# design.net
KiCad netlist of a schematic drawn in EasyEDA Pro
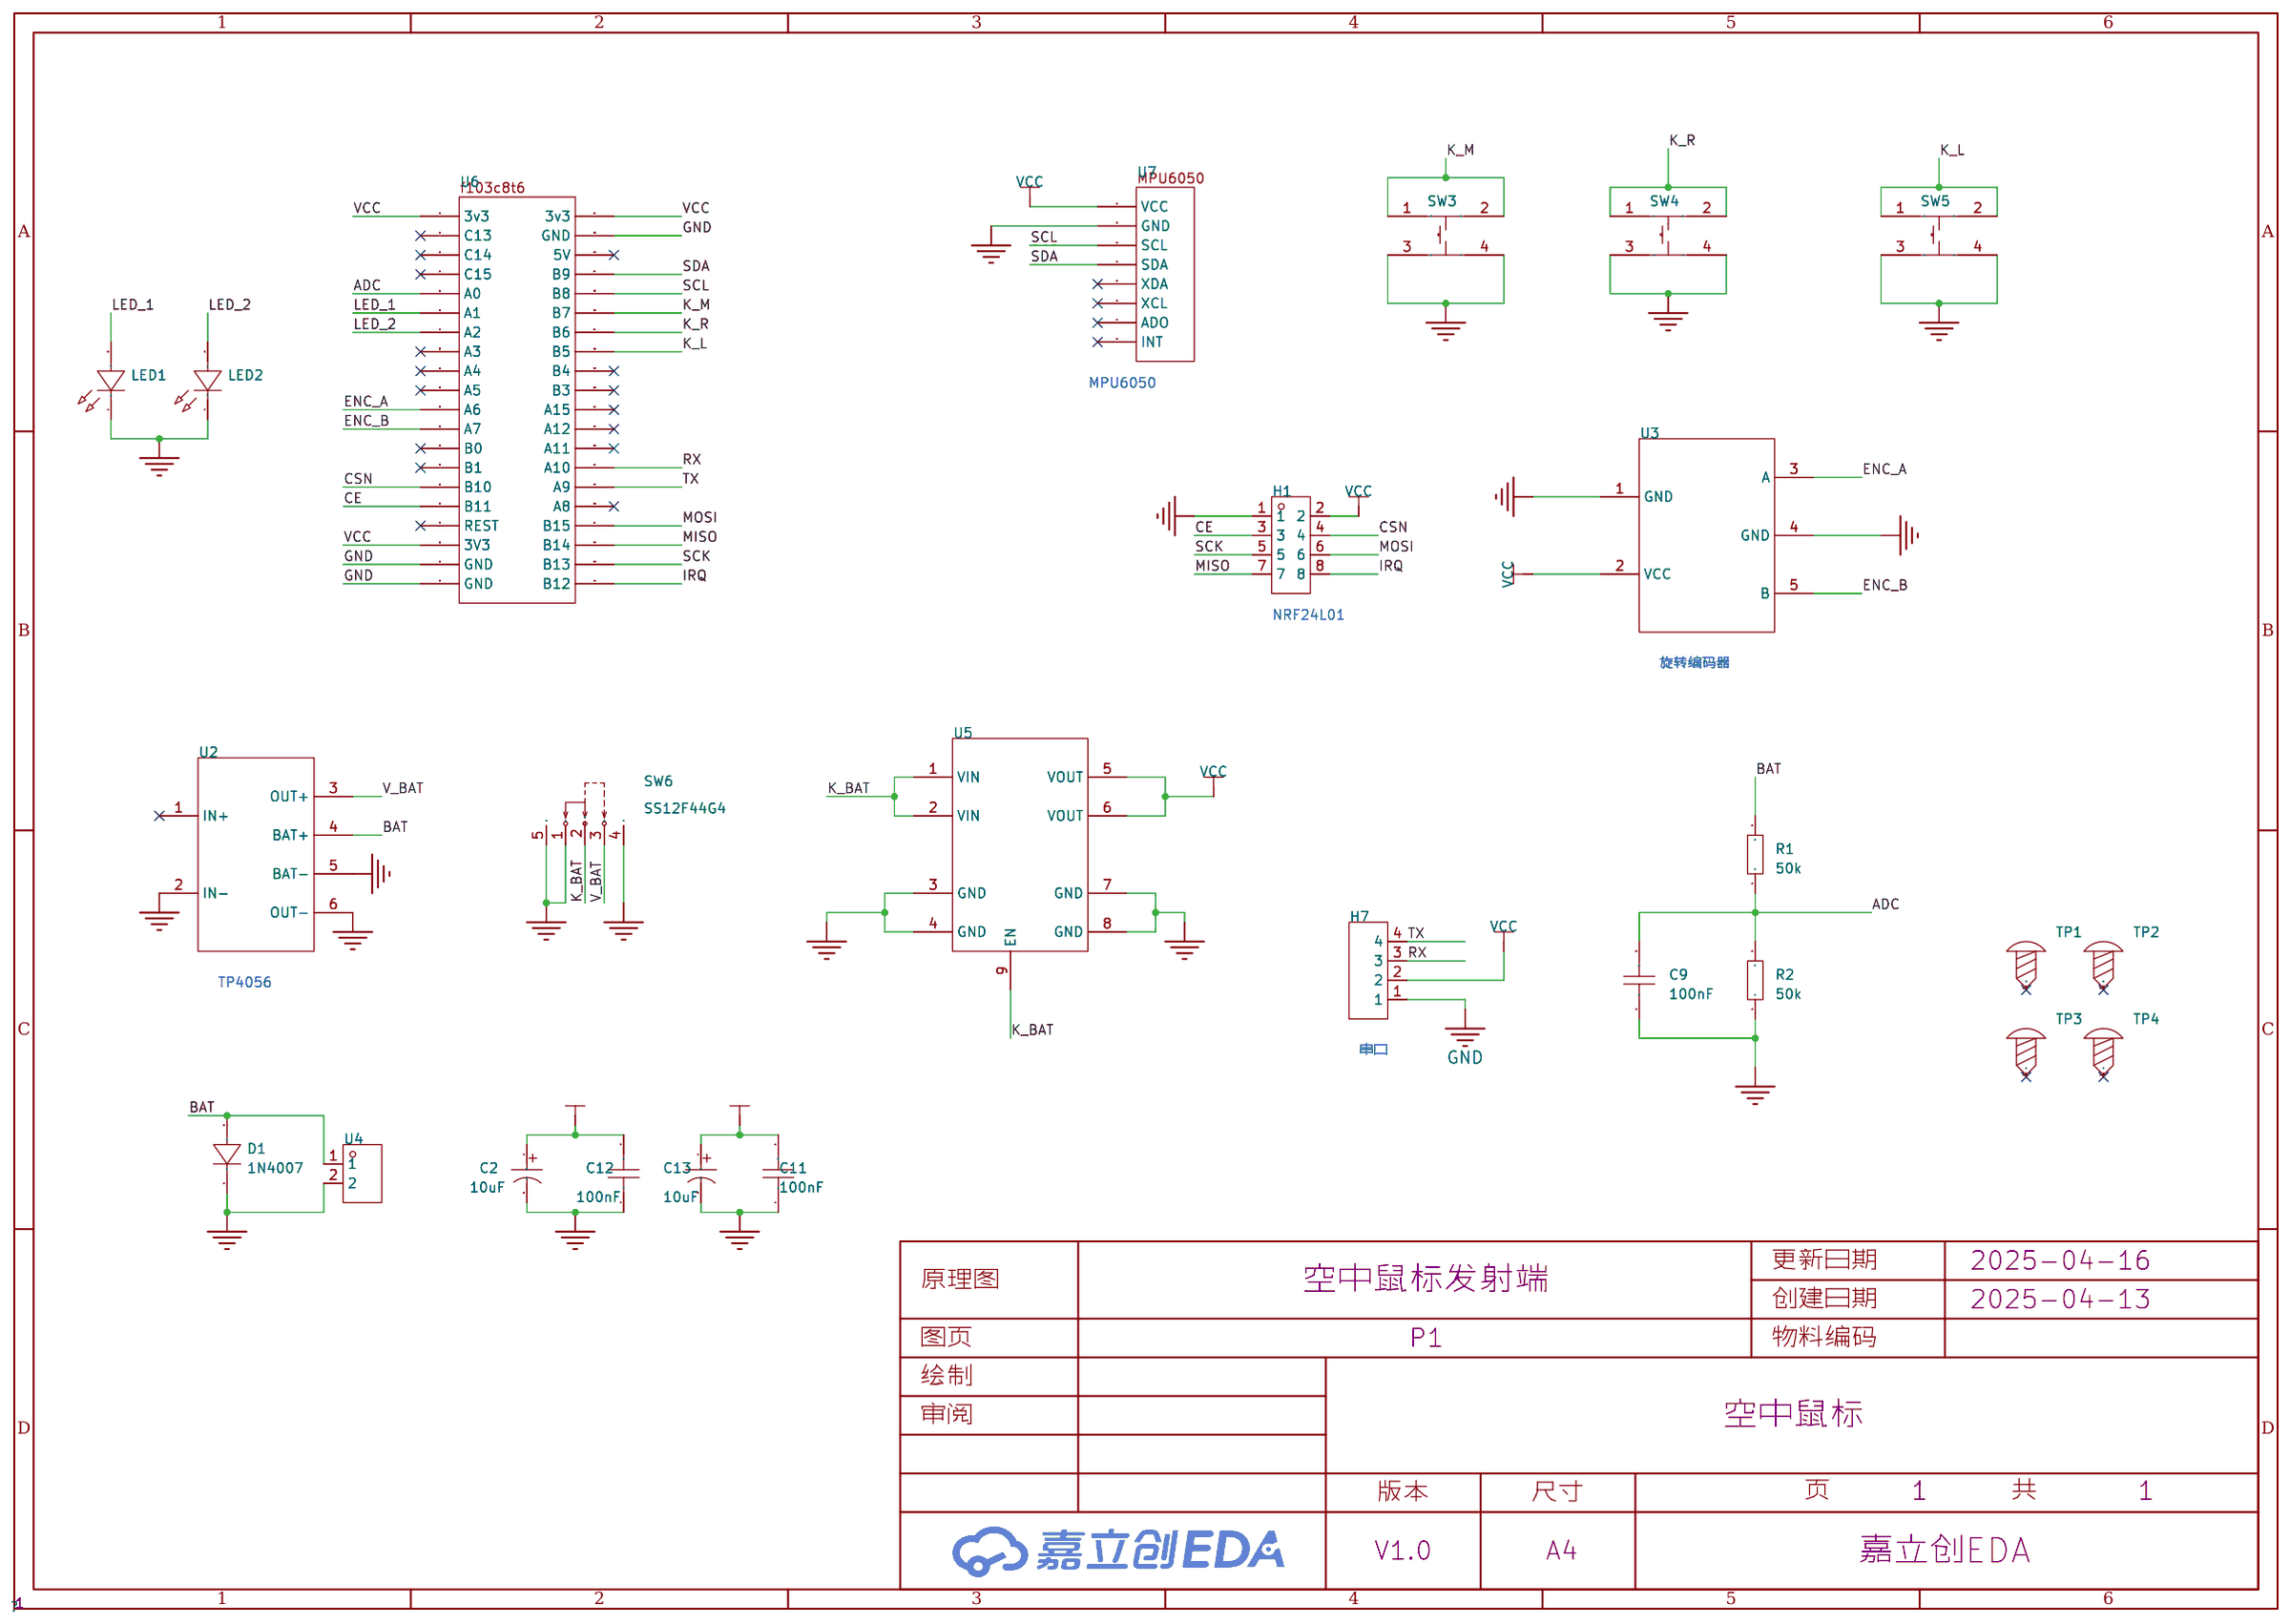
[diagram p0: schematic sheet]

(export (version "E")
  (design (tool "Eeschema 10.0.6"))
  (components
    (comp (ref "C2")
      (value "10uF")
      (footprint "easyedapro:CAP-SMD_BD4.0-L4.3-W4.3-FD")
      (description "容值:10uF;精度:±20%;额定电压:35V;纹波电流:15mA@120Hz;等效串联电阻(ESR):-;")
      (fields (field (name "Manufacturer Part") "RVT1V100M0405") (field (name "Manufacturer") "ROQANG(容强)"))
      (libsource (lib "easyedapro") (part "RVT1V100M0405-C72485"))
    )
    (comp (ref "C9")
      (value "100nF")
      (footprint "easyedapro:C0603")
      (libsource (lib "easyedapro") (part "CapAcitance"))
    )
    (comp (ref "C11")
      (value "100nF")
      (footprint "easyedapro:C0603")
      (description "容值:100nF;精度:±10%;额定电压:50V;材质(温度系数):X7R;")
      (fields
        (field (name "Manufacturer Part") "CC0603KRX7R9BB104")
        (field (name "Manufacturer") "YAGEO(国巨)")
      )
      (libsource (lib "easyedapro") (part "CC0603KRX7R9BB104"))
    )
    (comp (ref "C12")
      (value "100nF")
      (footprint "easyedapro:C0603")
      (description "容值:100nF;精度:±10%;额定电压:50V;材质(温度系数):X7R;")
      (fields
        (field (name "Manufacturer Part") "CC0603KRX7R9BB104")
        (field (name "Manufacturer") "YAGEO(国巨)")
      )
      (libsource (lib "easyedapro") (part "CC0603KRX7R9BB104"))
    )
    (comp (ref "C13")
      (value "10uF")
      (footprint "easyedapro:CAP-SMD_BD4.0-L4.3-W4.3-FD")
      (description "容值:10uF;精度:±20%;额定电压:35V;纹波电流:15mA@120Hz;等效串联电阻(ESR):-;")
      (fields (field (name "Manufacturer Part") "RVT1V100M0405") (field (name "Manufacturer") "ROQANG(容强)"))
      (libsource (lib "easyedapro") (part "RVT1V100M0405-C72485"))
    )
    (comp (ref "D1")
      (value "1N4007")
      (footprint "easyedapro:SMA_L4.3-W2.5-LS5.0-RD")
      (description "二极管配置:独立式;正向压降(Vf):1.1V@1A;直流反向耐压(Vr):1kV;整流电流:1A;")
      (fields (field (name "Manufacturer") "TWGMC(台湾迪嘉)"))
      (libsource (lib "easyedapro") (part "1N4007_C727081"))
    )
    (comp (ref "H1")
      (value "NRF24L01")
      (footprint "easyedapro:HDR-TH_8P-P2.54-V-F-R2-C4-S2.54")
      (fields (field (name "Manufacturer Part") "PM254V-12-08-H85") (field (name "Manufacturer") "XFCN(兴飞)"))
      (libsource (lib "easyedapro") (part "PM254V-12-08-H85_C2834799"))
    )
    (comp (ref "H7")
      (value "~")
      (footprint "easyedapro:HDR-TH_4P-P2.54-V-M")
      (libsource (lib "easyedapro") (part "PZ254V-11-04P"))
    )
    (comp (ref "LED1")
      (value "521-9210F")
      (footprint "easyedapro:LED-TH_BD3.0-P2.54-RD")
      (fields (field (name "Manufacturer") "Dialight"))
      (libsource (lib "easyedapro") (part "521-9210F"))
    )
    (comp (ref "LED2")
      (value "521-9210F")
      (footprint "easyedapro:LED-TH_BD3.0-P2.54-RD")
      (fields (field (name "Manufacturer") "Dialight"))
      (libsource (lib "easyedapro") (part "521-9210F"))
    )
    (comp (ref "R1") (value "50k") (footprint "easyedapro:R0603") (libsource (lib "easyedapro") (part "电阻")))
    (comp (ref "R2") (value "50k") (footprint "easyedapro:R0603") (libsource (lib "easyedapro") (part "电阻")))
    (comp (ref "SCREW1")
      (value "TP1")
      (footprint "easyedapro:M3螺丝")
      (libsource (lib "easyedapro") (part "螺丝孔"))
    )
    (comp (ref "SCREW2")
      (value "TP2")
      (footprint "easyedapro:M3螺丝")
      (libsource (lib "easyedapro") (part "螺丝孔"))
    )
    (comp (ref "SCREW3")
      (value "TP3")
      (footprint "easyedapro:M3螺丝")
      (libsource (lib "easyedapro") (part "螺丝孔"))
    )
    (comp (ref "SCREW4")
      (value "TP4")
      (footprint "easyedapro:M3螺丝")
      (libsource (lib "easyedapro") (part "螺丝孔"))
    )
    (comp (ref "SW3")
      (value "TS-1002-07026")
      (footprint "easyedapro:SW-TH_4P-L6.0-W6.0-P4.50-LS6.5")
      (description "电路结构:单刀单掷;按钮形状:圆形按钮;安装方式:直插;开关长度:6mm;开关宽度:6mm;开关高度:7mm;触点电流:50mA;额定电压(DC):12V;带灯:-;机械寿命:-;")
      (fields (field (name "Manufacturer") "XUNPU(讯普)"))
      (libsource (lib "easyedapro") (part "TS-1002-07026"))
    )
    (comp (ref "SW4")
      (value "TS-1002-07026")
      (footprint "easyedapro:SW-TH_4P-L6.0-W6.0-P4.50-LS6.5")
      (description "电路结构:单刀单掷;按钮形状:圆形按钮;安装方式:直插;开关长度:6mm;开关宽度:6mm;开关高度:7mm;触点电流:50mA;额定电压(DC):12V;带灯:-;机械寿命:-;")
      (fields (field (name "Manufacturer") "XUNPU(讯普)"))
      (libsource (lib "easyedapro") (part "TS-1002-07026"))
    )
    (comp (ref "SW5")
      (value "TS-1002-07026")
      (footprint "easyedapro:SW-TH_4P-L6.0-W6.0-P4.50-LS6.5")
      (description "电路结构:单刀单掷;按钮形状:圆形按钮;安装方式:直插;开关长度:6mm;开关宽度:6mm;开关高度:7mm;触点电流:50mA;额定电压(DC):12V;带灯:-;机械寿命:-;")
      (fields (field (name "Manufacturer") "XUNPU(讯普)"))
      (libsource (lib "easyedapro") (part "TS-1002-07026"))
    )
    (comp (ref "SW6")
      (value "SS12F44G4")
      (footprint "easyedapro:SW-TH_SHOU-HAN_SS12F44G4")
      (description "电路结构:单刀双掷;安装方式:直插;开关颜色:-;额定电流(DC):300mA;额定电压(DC):50V;额定电流(AC):-;额定电压(AC):-;机械寿命:5千次;")
      (fields (field (name "Manufacturer") "SHOU HAN(首韩)"))
      (libsource (lib "easyedapro") (part "SS12F44G4"))
    )
    (comp (ref "U2")
      (value "~")
      (footprint "easyedapro:TP4056")
      (libsource (lib "easyedapro") (part "TP4056模块"))
    )
    (comp (ref "U3") (value "~") (footprint "easyedapro:旋转编码器") (libsource (lib "easyedapro") (part "旋转编码器")))
    (comp (ref "U4")
      (value "XY-XHB2.54-2A21")
      (footprint "easyedapro:HDR-TH_2P-P2.50-H-F-W7.3-N")
      (description "插针结构:1x2P;间距:2.54mm;安装方式:弯插;总PIN数:2P;排数:1;每排PIN数:2;行距:2.54mm;额定电流:2A;工作温度范围:-25°C~+85°C;")
      (fields (field (name "Manufacturer") "XYECONN(辛译)"))
      (libsource (lib "easyedapro") (part "XY-XHB2.54-2A21"))
    )
    (comp (ref "U5")
      (value "~")
      (footprint "easyedapro:TPS63000")
      (libsource (lib "easyedapro") (part "TPS63000"))
    )
    (comp (ref "U6")
      (value "~")
      (footprint "easyedapro:stm32f103c8t6最小系统板")
      (libsource (lib "easyedapro") (part "stm32f103c8t6最小系统板"))
    )
    (comp (ref "U7")
      (value "~")
      (footprint "easyedapro:MPU6050")
      (libsource (lib "easyedapro") (part "MPU6050"))
    )
  )
  (nets
    (net (code "1") (name "/ADC") (class "Default")
      (node (ref "C9") (pin "2") (pinfunction "2_2") (pintype "input"))
      (node (ref "R1") (pin "1") (pinfunction "1_1") (pintype "input"))
      (node (ref "R2") (pin "2") (pinfunction "2_2") (pintype "input"))
      (node (ref "U6") (pin "5") (pinfunction "A0_5") (pintype "input"))
    )
    (net (code "2") (name "/BAT") (class "Default")
      (node (ref "D1") (pin "2") (pinfunction "A_2") (pintype "unspecified"))
      (node (ref "R1") (pin "2") (pinfunction "2_2") (pintype "input"))
      (node (ref "U2") (pin "4") (pinfunction "BAT+_4") (pintype "input"))
      (node (ref "U4") (pin "1") (pinfunction "1_1") (pintype "unspecified"))
    )
    (net (code "3") (name "/CE") (class "Default")
      (node (ref "H1") (pin "3") (pinfunction "3_3") (pintype "unspecified"))
      (node (ref "U6") (pin "16") (pinfunction "B11_16") (pintype "input"))
    )
    (net (code "4") (name "/CSN") (class "Default")
      (node (ref "H1") (pin "4") (pinfunction "4_4") (pintype "unspecified"))
      (node (ref "U6") (pin "15") (pinfunction "B10_15") (pintype "input"))
    )
    (net (code "5") (name "/ENC_A") (class "Default")
      (node (ref "U3") (pin "3") (pinfunction "A_3") (pintype "input"))
      (node (ref "U6") (pin "11") (pinfunction "A6_11") (pintype "input"))
    )
    (net (code "6") (name "/ENC_B") (class "Default")
      (node (ref "U3") (pin "5") (pinfunction "B_5") (pintype "input"))
      (node (ref "U6") (pin "12") (pinfunction "A7_12") (pintype "input"))
    )
    (net (code "7") (name "/IRQ") (class "Default")
      (node (ref "H1") (pin "8") (pinfunction "8_8") (pintype "unspecified"))
      (node (ref "U6") (pin "40") (pinfunction "B12_40") (pintype "input"))
    )
    (net (code "8") (name "/K_L") (class "Default")
      (node (ref "SW5") (pin "1") (pinfunction "1_1") (pintype "unspecified"))
      (node (ref "SW5") (pin "2") (pinfunction "2_2") (pintype "unspecified"))
      (node (ref "U6") (pin "28") (pinfunction "B5_28") (pintype "input"))
    )
    (net (code "9") (name "/K_M") (class "Default")
      (node (ref "SW3") (pin "1") (pinfunction "1_1") (pintype "unspecified"))
      (node (ref "SW3") (pin "2") (pinfunction "2_2") (pintype "unspecified"))
      (node (ref "U6") (pin "26") (pinfunction "B7_26") (pintype "input"))
    )
    (net (code "10") (name "/K_R") (class "Default")
      (node (ref "SW4") (pin "1") (pinfunction "1_1") (pintype "unspecified"))
      (node (ref "SW4") (pin "2") (pinfunction "2_2") (pintype "unspecified"))
      (node (ref "U6") (pin "27") (pinfunction "B6_27") (pintype "input"))
    )
    (net (code "11") (name "/LED_1") (class "Default")
      (node (ref "LED1") (pin "2") (pinfunction "A_2") (pintype "unspecified"))
      (node (ref "U6") (pin "6") (pinfunction "A1_6") (pintype "input"))
    )
    (net (code "12") (name "/LED_2") (class "Default")
      (node (ref "LED2") (pin "2") (pinfunction "A_2") (pintype "unspecified"))
      (node (ref "U6") (pin "7") (pinfunction "A2_7") (pintype "input"))
    )
    (net (code "13") (name "/MISO") (class "Default")
      (node (ref "H1") (pin "7") (pinfunction "7_7") (pintype "unspecified"))
      (node (ref "U6") (pin "38") (pinfunction "B14_38") (pintype "input"))
    )
    (net (code "14") (name "/MOSI") (class "Default")
      (node (ref "H1") (pin "6") (pinfunction "6_6") (pintype "unspecified"))
      (node (ref "U6") (pin "37") (pinfunction "B15_37") (pintype "input"))
    )
    (net (code "15") (name "/RX") (class "Default")
      (node (ref "H7") (pin "3") (pinfunction "3_3") (pintype "unspecified"))
      (node (ref "U6") (pin "34") (pinfunction "A10_34") (pintype "input"))
    )
    (net (code "16") (name "/SCK") (class "Default")
      (node (ref "H1") (pin "5") (pinfunction "5_5") (pintype "unspecified"))
      (node (ref "U6") (pin "39") (pinfunction "B13_39") (pintype "input"))
    )
    (net (code "17") (name "/SCL") (class "Default")
      (node (ref "U6") (pin "25") (pinfunction "B8_25") (pintype "input"))
      (node (ref "U7") (pin "3") (pinfunction "SCL_3") (pintype "input"))
    )
    (net (code "18") (name "/SDA") (class "Default")
      (node (ref "U6") (pin "24") (pinfunction "B9_24") (pintype "input"))
      (node (ref "U7") (pin "4") (pinfunction "SDA_4") (pintype "input"))
    )
    (net (code "19") (name "/TX") (class "Default")
      (node (ref "H7") (pin "4") (pinfunction "4_4") (pintype "unspecified"))
      (node (ref "U6") (pin "35") (pinfunction "A9_35") (pintype "input"))
    )
    (net (code "20") (name "/V_BAT") (class "Default")
      (node (ref "SW6") (pin "3") (pinfunction "3_3") (pintype "unspecified"))
      (node (ref "U2") (pin "3") (pinfunction "OUT+_3") (pintype "input"))
    )
    (net (code "21") (name "GND") (class "Default")
      (node (ref "C11") (pin "1") (pinfunction "1_1") (pintype "unspecified"))
      (node (ref "C12") (pin "1") (pinfunction "1_1") (pintype "unspecified"))
      (node (ref "C13") (pin "2") (pinfunction "2_2") (pintype "input"))
      (node (ref "C2") (pin "2") (pinfunction "2_2") (pintype "input"))
      (node (ref "C9") (pin "1") (pinfunction "1_1") (pintype "input"))
      (node (ref "D1") (pin "1") (pinfunction "K_1") (pintype "unspecified"))
      (node (ref "H1") (pin "1") (pinfunction "1_1") (pintype "unspecified"))
      (node (ref "H7") (pin "1") (pinfunction "1_1") (pintype "unspecified"))
      (node (ref "LED1") (pin "1") (pinfunction "K_1") (pintype "unspecified"))
      (node (ref "LED2") (pin "1") (pinfunction "K_1") (pintype "unspecified"))
      (node (ref "R2") (pin "1") (pinfunction "1_1") (pintype "input"))
      (node (ref "SW3") (pin "3") (pinfunction "3_3") (pintype "unspecified"))
      (node (ref "SW3") (pin "4") (pinfunction "4_4") (pintype "unspecified"))
      (node (ref "SW4") (pin "3") (pinfunction "3_3") (pintype "unspecified"))
      (node (ref "SW4") (pin "4") (pinfunction "4_4") (pintype "unspecified"))
      (node (ref "SW5") (pin "3") (pinfunction "3_3") (pintype "unspecified"))
      (node (ref "SW5") (pin "4") (pinfunction "4_4") (pintype "unspecified"))
      (node (ref "SW6") (pin "1") (pinfunction "1_1") (pintype "unspecified"))
      (node (ref "SW6") (pin "4") (pinfunction "4_4") (pintype "unspecified"))
      (node (ref "SW6") (pin "5") (pinfunction "5_5") (pintype "unspecified"))
      (node (ref "U2") (pin "2") (pinfunction "IN-_2") (pintype "input"))
      (node (ref "U2") (pin "5") (pinfunction "BAT-_5") (pintype "input"))
      (node (ref "U2") (pin "6") (pinfunction "OUT-_6") (pintype "input"))
      (node (ref "U3") (pin "1") (pinfunction "GND_1") (pintype "input"))
      (node (ref "U3") (pin "4") (pinfunction "GND_4") (pintype "input"))
      (node (ref "U4") (pin "2") (pinfunction "2_2") (pintype "unspecified"))
      (node (ref "U5") (pin "3") (pinfunction "GND_3") (pintype "input"))
      (node (ref "U5") (pin "4") (pinfunction "GND_4") (pintype "input"))
      (node (ref "U5") (pin "7") (pinfunction "GND_7") (pintype "input"))
      (node (ref "U5") (pin "8") (pinfunction "GND_8") (pintype "input"))
      (node (ref "U6") (pin "19") (pinfunction "GND_19") (pintype "input"))
      (node (ref "U6") (pin "20") (pinfunction "GND_20") (pintype "input"))
      (node (ref "U6") (pin "22") (pinfunction "GND_22") (pintype "input"))
      (node (ref "U7") (pin "2") (pinfunction "GND_2") (pintype "input"))
    )
    (net (code "22") (name "K_BAT") (class "Default")
      (node (ref "C12") (pin "2") (pinfunction "2_2") (pintype "unspecified"))
      (node (ref "C2") (pin "1") (pinfunction "1_1") (pintype "input"))
      (node (ref "SW6") (pin "2") (pinfunction "2_2") (pintype "unspecified"))
      (node (ref "U5") (pin "1") (pinfunction "VIN_1") (pintype "input"))
      (node (ref "U5") (pin "2") (pinfunction "VIN_2") (pintype "input"))
      (node (ref "U5") (pin "9") (pinfunction "EN_9") (pintype "input"))
    )
    (net (code "23") (name "VCC") (class "Default")
      (node (ref "C11") (pin "2") (pinfunction "2_2") (pintype "unspecified"))
      (node (ref "C13") (pin "1") (pinfunction "1_1") (pintype "input"))
      (node (ref "H1") (pin "2") (pinfunction "2_2") (pintype "unspecified"))
      (node (ref "H7") (pin "2") (pinfunction "2_2") (pintype "unspecified"))
      (node (ref "U3") (pin "2") (pinfunction "VCC_2") (pintype "input"))
      (node (ref "U5") (pin "5") (pinfunction "VOUT_5") (pintype "input"))
      (node (ref "U5") (pin "6") (pinfunction "VOUT_6") (pintype "input"))
      (node (ref "U6") (pin "1") (pinfunction "3v3_1") (pintype "input"))
      (node (ref "U6") (pin "18") (pinfunction "3V3_18") (pintype "input"))
      (node (ref "U6") (pin "21") (pinfunction "3v3_21") (pintype "input"))
      (node (ref "U7") (pin "1") (pinfunction "VCC_1") (pintype "input"))
    )
    (net (code "24") (name "unconnected-(SCREW1-Pad1)") (class "Default")
      (node (ref "SCREW1") (pin "1") (pinfunction "1_1") (pintype "input+no_connect"))
    )
    (net (code "25") (name "unconnected-(SCREW2-Pad1)") (class "Default")
      (node (ref "SCREW2") (pin "1") (pinfunction "1_1") (pintype "input+no_connect"))
    )
    (net (code "26") (name "unconnected-(SCREW3-Pad1)") (class "Default")
      (node (ref "SCREW3") (pin "1") (pinfunction "1_1") (pintype "input+no_connect"))
    )
    (net (code "27") (name "unconnected-(SCREW4-Pad1)") (class "Default")
      (node (ref "SCREW4") (pin "1") (pinfunction "1_1") (pintype "input+no_connect"))
    )
    (net (code "28") (name "unconnected-(U2-IN+-Pad1)") (class "Default")
      (node (ref "U2") (pin "1") (pinfunction "IN+_1") (pintype "input+no_connect"))
    )
    (net (code "29") (name "unconnected-(U6-5V-Pad23)") (class "Default")
      (node (ref "U6") (pin "23") (pinfunction "5V_23") (pintype "input+no_connect"))
    )
    (net (code "30") (name "unconnected-(U6-A3-Pad8)") (class "Default")
      (node (ref "U6") (pin "8") (pinfunction "A3_8") (pintype "input+no_connect"))
    )
    (net (code "31") (name "unconnected-(U6-A4-Pad9)") (class "Default")
      (node (ref "U6") (pin "9") (pinfunction "A4_9") (pintype "input+no_connect"))
    )
    (net (code "32") (name "unconnected-(U6-A5-Pad10)") (class "Default")
      (node (ref "U6") (pin "10") (pinfunction "A5_10") (pintype "input+no_connect"))
    )
    (net (code "33") (name "unconnected-(U6-A8-Pad36)") (class "Default")
      (node (ref "U6") (pin "36") (pinfunction "A8_36") (pintype "input+no_connect"))
    )
    (net (code "34") (name "unconnected-(U6-A11-Pad33)") (class "Default")
      (node (ref "U6") (pin "33") (pinfunction "A11_33") (pintype "input+no_connect"))
    )
    (net (code "35") (name "unconnected-(U6-A12-Pad32)") (class "Default")
      (node (ref "U6") (pin "32") (pinfunction "A12_32") (pintype "input+no_connect"))
    )
    (net (code "36") (name "unconnected-(U6-A15-Pad31)") (class "Default")
      (node (ref "U6") (pin "31") (pinfunction "A15_31") (pintype "input+no_connect"))
    )
    (net (code "37") (name "unconnected-(U6-B0-Pad13)") (class "Default")
      (node (ref "U6") (pin "13") (pinfunction "B0_13") (pintype "input+no_connect"))
    )
    (net (code "38") (name "unconnected-(U6-B1-Pad14)") (class "Default")
      (node (ref "U6") (pin "14") (pinfunction "B1_14") (pintype "input+no_connect"))
    )
    (net (code "39") (name "unconnected-(U6-B3-Pad30)") (class "Default")
      (node (ref "U6") (pin "30") (pinfunction "B3_30") (pintype "input+no_connect"))
    )
    (net (code "40") (name "unconnected-(U6-B4-Pad29)") (class "Default")
      (node (ref "U6") (pin "29") (pinfunction "B4_29") (pintype "input+no_connect"))
    )
    (net (code "41") (name "unconnected-(U6-C13-Pad2)") (class "Default")
      (node (ref "U6") (pin "2") (pinfunction "C13_2") (pintype "input+no_connect"))
    )
    (net (code "42") (name "unconnected-(U6-C14-Pad3)") (class "Default")
      (node (ref "U6") (pin "3") (pinfunction "C14_3") (pintype "input+no_connect"))
    )
    (net (code "43") (name "unconnected-(U6-C15-Pad4)") (class "Default")
      (node (ref "U6") (pin "4") (pinfunction "C15_4") (pintype "input+no_connect"))
    )
    (net (code "44") (name "unconnected-(U6-REST-Pad17)") (class "Default")
      (node (ref "U6") (pin "17") (pinfunction "REST_17") (pintype "input+no_connect"))
    )
    (net (code "45") (name "unconnected-(U7-ADO-Pad7)") (class "Default")
      (node (ref "U7") (pin "7") (pinfunction "ADO_7") (pintype "input+no_connect"))
    )
    (net (code "46") (name "unconnected-(U7-INT-Pad8)") (class "Default")
      (node (ref "U7") (pin "8") (pinfunction "INT_8") (pintype "input+no_connect"))
    )
    (net (code "47") (name "unconnected-(U7-XCL-Pad6)") (class "Default")
      (node (ref "U7") (pin "6") (pinfunction "XCL_6") (pintype "input+no_connect"))
    )
    (net (code "48") (name "unconnected-(U7-XDA-Pad5)") (class "Default")
      (node (ref "U7") (pin "5") (pinfunction "XDA_5") (pintype "input+no_connect"))
    )
  )
)
